# akabeacon_circle_ble113.net
KiCad netlist of a schematic drawn in EAGLE
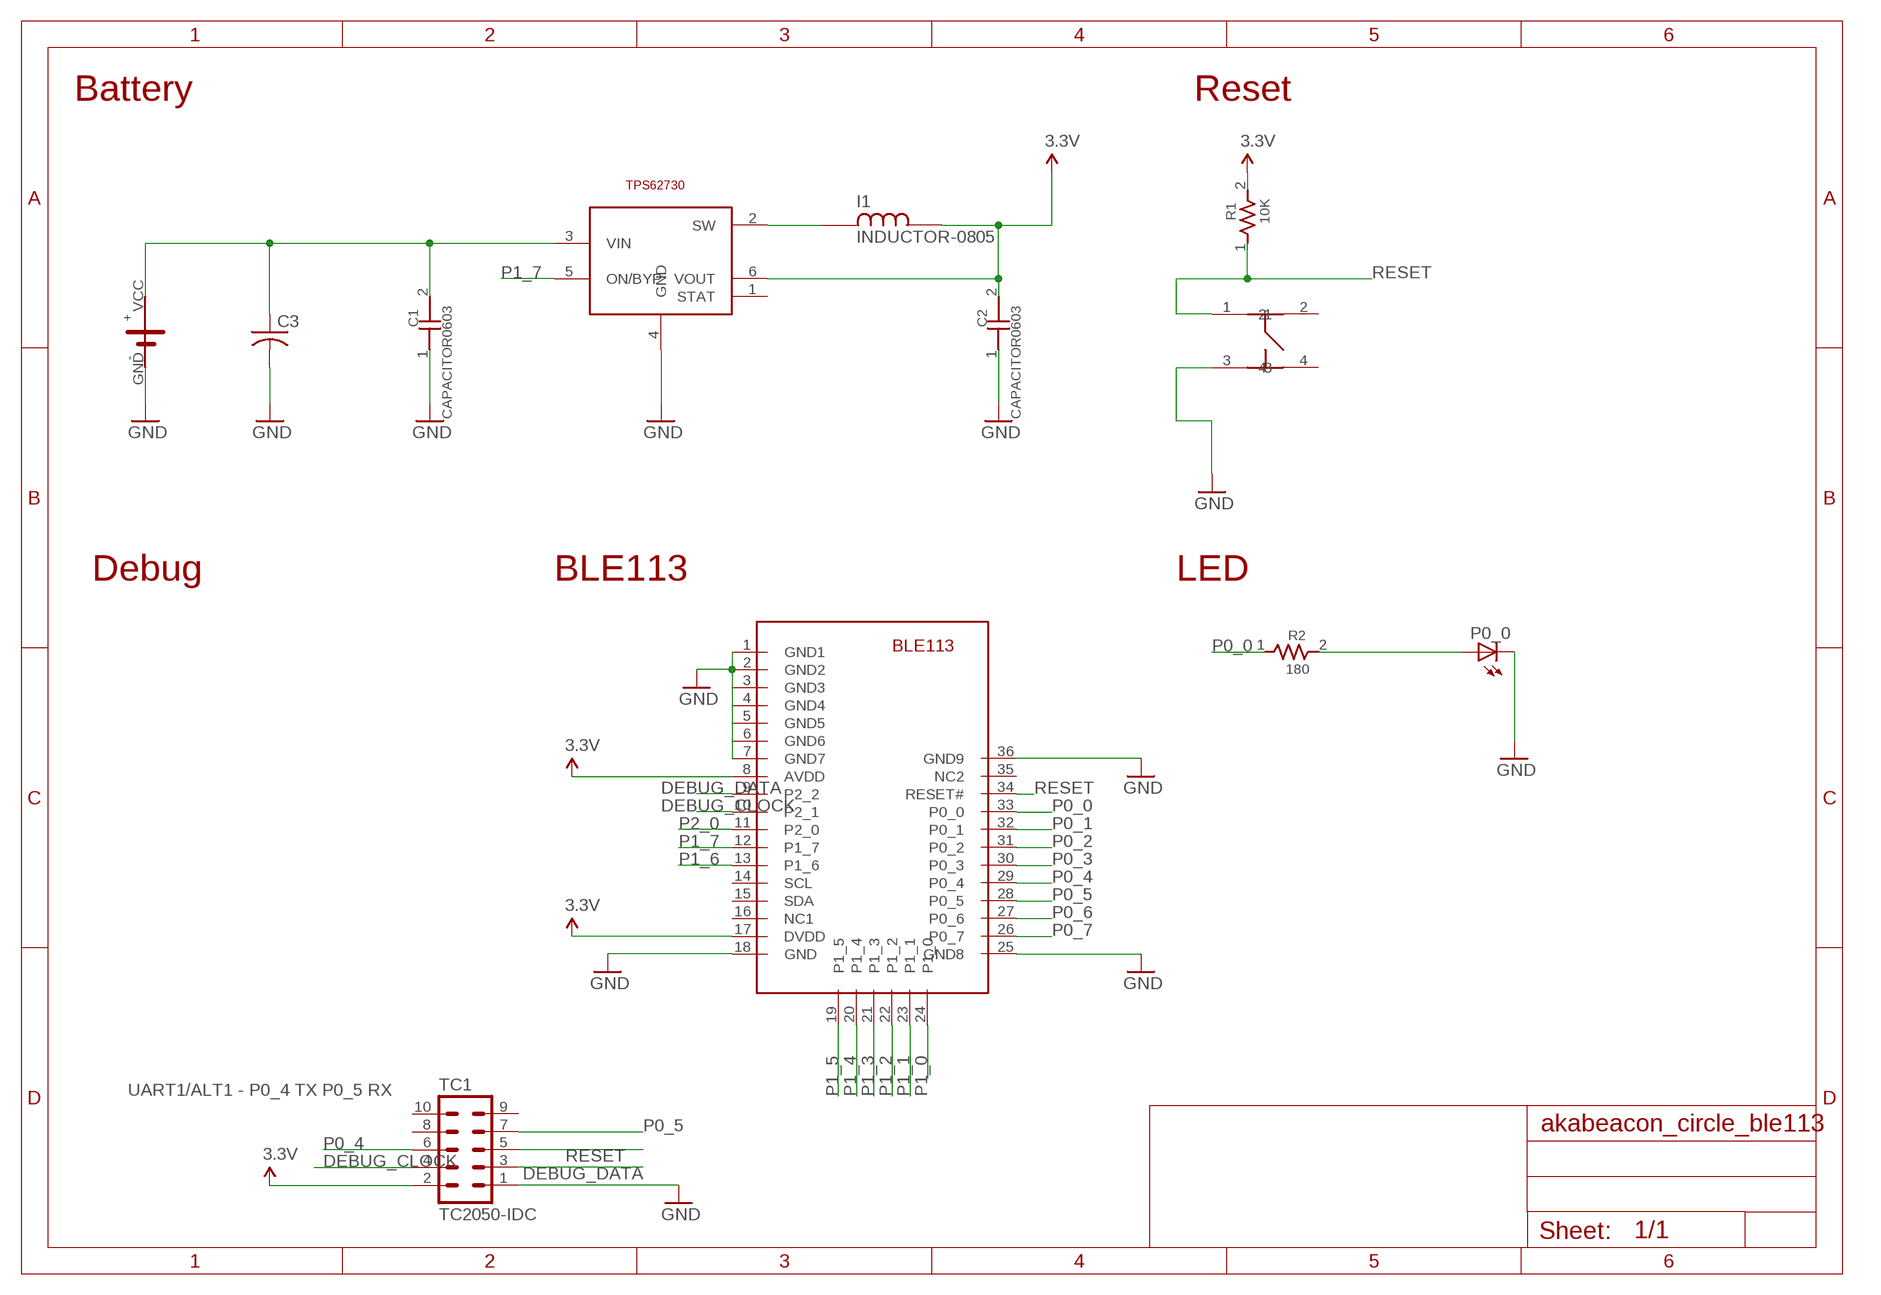
[diagram p0: schematic, sheet 1]

(export (version "E")
  (design (tool "Eeschema 10.0.6"))
  (components
    (comp (ref "C1")
      (value "CAPACITOR0603")
      (footprint "eagle-import:0603")
      (libsource (lib "eagle-import") (part "CAPACITOR0603"))
    )
    (comp (ref "C2")
      (value "CAPACITOR0603")
      (footprint "eagle-import:0603")
      (libsource (lib "eagle-import") (part "CAPACITOR0603"))
    )
    (comp (ref "C3")
      (value "C-USC3225")
      (footprint "eagle-import:C3225")
      (libsource (lib "eagle-import") (part "C-USC3225"))
    )
    (comp (ref "I1")
      (value "INDUCTOR-0805")
      (footprint "eagle-import:INDUCTOR-0805")
      (libsource (lib "eagle-import") (part "INDUCTOR-0805"))
    )
    (comp (ref "P0_0")
      (value "LEDCHIP-LED0603")
      (footprint "eagle-import:CHIP-LED0603")
      (libsource (lib "eagle-import") (part "LEDCHIP-LED0603"))
    )
    (comp (ref "R1")
      (value "10K")
      (footprint "eagle-import:0603")
      (libsource (lib "eagle-import") (part "RESISTOR0603"))
    )
    (comp (ref "R2")
      (value "180")
      (footprint "eagle-import:0603")
      (libsource (lib "eagle-import") (part "RESISTOR0603"))
    )
    (comp (ref "TC1")
      (value "TC2050-IDC")
      (footprint "eagle-import:TC2050-IDC-NL")
      (libsource (lib "eagle-import") (part "TC2050-IDC"))
    )
    (comp (ref "TPS1")
      (value "TI-TPS62730")
      (footprint "eagle-import:TI-TPS62730")
      (libsource (lib "eagle-import") (part "TI-TPS62730"))
    )
    (comp (ref "U$1")
      (value "CIRCLE-TYPE1")
      (footprint "eagle-import:CIRCLE-TYE1-TC2030")
      (libsource (lib "eagle-import") (part "CIRCLE-TYPE1"))
    )
    (comp (ref "U$4")
      (value "BLE113")
      (footprint "eagle-import:BLE113")
      (libsource (lib "eagle-import") (part "BLE113"))
    )
    (comp (ref "U$5")
      (value "SWICTH-4P(KMR2)")
      (footprint "eagle-import:SWITCH-4P(KMR2)")
      (libsource (lib "eagle-import") (part "SWICTH-4P(KMR2)"))
    )
  )
  (nets
    (net (code "1") (name "/DEBUG_CLOCK") (class "Default")
      (node (ref "TC1") (pin "4") (pinfunction "4_4") (pintype "passive"))
      (node (ref "U$4") (pin "10") (pinfunction "P2_1_10") (pintype "bidirectional"))
    )
    (net (code "2") (name "/DEBUG_DATA") (class "Default")
      (node (ref "TC1") (pin "3") (pinfunction "3_3") (pintype "passive"))
      (node (ref "U$4") (pin "9") (pinfunction "P2_2_9") (pintype "bidirectional"))
    )
    (net (code "3") (name "/P0_0") (class "Default")
      (node (ref "R2") (pin "1") (pinfunction "1_1") (pintype "passive"))
      (node (ref "U$4") (pin "33") (pinfunction "P0_0_33") (pintype "bidirectional"))
    )
    (net (code "4") (name "/P0_1") (class "Default")
      (node (ref "U$4") (pin "32") (pinfunction "P0_1_32") (pintype "bidirectional"))
    )
    (net (code "5") (name "/P0_2") (class "Default")
      (node (ref "U$4") (pin "31") (pinfunction "P0_2_31") (pintype "bidirectional"))
    )
    (net (code "6") (name "/P0_3") (class "Default")
      (node (ref "U$4") (pin "30") (pinfunction "P0_3_30") (pintype "bidirectional"))
    )
    (net (code "7") (name "/P0_4") (class "Default")
      (node (ref "TC1") (pin "6") (pinfunction "6_6") (pintype "passive"))
      (node (ref "U$4") (pin "29") (pinfunction "P0_4_29") (pintype "bidirectional"))
    )
    (net (code "8") (name "/P0_5") (class "Default")
      (node (ref "TC1") (pin "7") (pinfunction "7_7") (pintype "passive"))
      (node (ref "U$4") (pin "28") (pinfunction "P0_5_28") (pintype "bidirectional"))
    )
    (net (code "9") (name "/P0_6") (class "Default")
      (node (ref "U$4") (pin "27") (pinfunction "P0_6_27") (pintype "bidirectional"))
    )
    (net (code "10") (name "/P0_7") (class "Default")
      (node (ref "U$4") (pin "26") (pinfunction "P0_7_26") (pintype "bidirectional"))
    )
    (net (code "11") (name "/P1_0") (class "Default")
      (node (ref "U$4") (pin "24") (pinfunction "P1_0_24") (pintype "bidirectional"))
    )
    (net (code "12") (name "/P1_1") (class "Default")
      (node (ref "U$4") (pin "23") (pinfunction "P1_1_23") (pintype "bidirectional"))
    )
    (net (code "13") (name "/P1_2") (class "Default")
      (node (ref "U$4") (pin "22") (pinfunction "P1_2_22") (pintype "bidirectional"))
    )
    (net (code "14") (name "/P1_3") (class "Default")
      (node (ref "U$4") (pin "21") (pinfunction "P1_3_21") (pintype "bidirectional"))
    )
    (net (code "15") (name "/P1_4") (class "Default")
      (node (ref "U$4") (pin "20") (pinfunction "P1_4_20") (pintype "bidirectional"))
    )
    (net (code "16") (name "/P1_5") (class "Default")
      (node (ref "U$4") (pin "19") (pinfunction "P1_5_19") (pintype "bidirectional"))
    )
    (net (code "17") (name "/P1_6") (class "Default")
      (node (ref "U$4") (pin "13") (pinfunction "P1_6_13") (pintype "bidirectional"))
    )
    (net (code "18") (name "/P1_7") (class "Default")
      (node (ref "TPS1") (pin "5") (pinfunction "ON/BYP_5") (pintype "bidirectional"))
      (node (ref "U$4") (pin "12") (pinfunction "P1_7_12") (pintype "bidirectional"))
    )
    (net (code "19") (name "/P2_0") (class "Default")
      (node (ref "U$4") (pin "11") (pinfunction "P2_0_11") (pintype "bidirectional"))
    )
    (net (code "20") (name "/RESET") (class "Default")
      (node (ref "R1") (pin "1") (pinfunction "1_1") (pintype "passive"))
      (node (ref "TC1") (pin "5") (pinfunction "5_5") (pintype "passive"))
      (node (ref "U$4") (pin "34") (pinfunction "RESET#_34") (pintype "bidirectional"))
      (node (ref "U$5") (pin "1") (pinfunction "1_1") (pintype "bidirectional"))
    )
    (net (code "21") (name "3.3V") (class "Default")
      (node (ref "C2") (pin "2") (pinfunction "2_2") (pintype "passive"))
      (node (ref "I1") (pin "P$2") (pinfunction "P$2_P$2") (pintype "bidirectional"))
      (node (ref "R1") (pin "2") (pinfunction "2_2") (pintype "passive"))
      (node (ref "TC1") (pin "2") (pinfunction "2_2") (pintype "passive"))
      (node (ref "TPS1") (pin "6") (pinfunction "VOUT_6") (pintype "bidirectional"))
      (node (ref "U$4") (pin "17") (pinfunction "DVDD_17") (pintype "bidirectional"))
      (node (ref "U$4") (pin "8") (pinfunction "AVDD_8") (pintype "bidirectional"))
    )
    (net (code "22") (name "GND") (class "Default")
      (node (ref "C1") (pin "1") (pinfunction "1_1") (pintype "passive"))
      (node (ref "C2") (pin "1") (pinfunction "1_1") (pintype "passive"))
      (node (ref "C3") (pin "2") (pinfunction "2_2") (pintype "passive"))
      (node (ref "P0_0") (pin "C") (pinfunction "C_C") (pintype "passive"))
      (node (ref "TC1") (pin "1") (pinfunction "1_1") (pintype "passive"))
      (node (ref "TPS1") (pin "4") (pinfunction "GND_4") (pintype "bidirectional"))
      (node (ref "U$1") (pin "GND") (pinfunction "GND_GND") (pintype "bidirectional"))
      (node (ref "U$4") (pin "1") (pinfunction "GND1_1") (pintype "bidirectional"))
      (node (ref "U$4") (pin "18") (pinfunction "GND_18") (pintype "bidirectional"))
      (node (ref "U$4") (pin "2") (pinfunction "GND2_2") (pintype "bidirectional"))
      (node (ref "U$4") (pin "25") (pinfunction "GND8_25") (pintype "bidirectional"))
      (node (ref "U$4") (pin "3") (pinfunction "GND3_3") (pintype "bidirectional"))
      (node (ref "U$4") (pin "36") (pinfunction "GND9_36") (pintype "bidirectional"))
      (node (ref "U$4") (pin "4") (pinfunction "GND4_4") (pintype "bidirectional"))
      (node (ref "U$4") (pin "5") (pinfunction "GND5_5") (pintype "bidirectional"))
      (node (ref "U$4") (pin "6") (pinfunction "GND6_6") (pintype "bidirectional"))
      (node (ref "U$4") (pin "7") (pinfunction "GND7_7") (pintype "bidirectional"))
      (node (ref "U$5") (pin "3") (pinfunction "3_3") (pintype "bidirectional"))
    )
    (net (code "23") (name "Net-(P0_0-PadA)") (class "Default")
      (node (ref "P0_0") (pin "A") (pinfunction "A_A") (pintype "passive"))
      (node (ref "R2") (pin "2") (pinfunction "2_2") (pintype "passive"))
    )
    (net (code "24") (name "Net-(TPS1-SW)") (class "Default")
      (node (ref "I1") (pin "P$1") (pinfunction "P$1_P$1") (pintype "bidirectional"))
      (node (ref "TPS1") (pin "2") (pinfunction "SW_2") (pintype "bidirectional"))
    )
    (net (code "25") (name "Net-(TPS1-VIN)") (class "Default")
      (node (ref "C1") (pin "2") (pinfunction "2_2") (pintype "passive"))
      (node (ref "C3") (pin "1") (pinfunction "1_1") (pintype "passive"))
      (node (ref "TPS1") (pin "3") (pinfunction "VIN_3") (pintype "bidirectional"))
      (node (ref "U$1") (pin "VCC") (pinfunction "VCC_VCC") (pintype "bidirectional"))
    )
    (net (code "26") (name "unconnected-(TC1-Pad8)") (class "Default")
      (node (ref "TC1") (pin "8") (pinfunction "8_8") (pintype "passive"))
    )
    (net (code "27") (name "unconnected-(TC1-Pad9)") (class "Default")
      (node (ref "TC1") (pin "9") (pinfunction "9_9") (pintype "passive"))
    )
    (net (code "28") (name "unconnected-(TC1-Pad10)") (class "Default")
      (node (ref "TC1") (pin "10") (pinfunction "10_10") (pintype "passive"))
    )
    (net (code "29") (name "unconnected-(TPS1-STAT-Pad1)") (class "Default")
      (node (ref "TPS1") (pin "1") (pinfunction "STAT_1") (pintype "bidirectional"))
    )
    (net (code "30") (name "unconnected-(U$4-NC1-Pad16)") (class "Default")
      (node (ref "U$4") (pin "16") (pinfunction "NC1_16") (pintype "bidirectional"))
    )
    (net (code "31") (name "unconnected-(U$4-NC2-Pad35)") (class "Default")
      (node (ref "U$4") (pin "35") (pinfunction "NC2_35") (pintype "bidirectional"))
    )
    (net (code "32") (name "unconnected-(U$4-SCL-Pad14)") (class "Default")
      (node (ref "U$4") (pin "14") (pinfunction "SCL_14") (pintype "bidirectional"))
    )
    (net (code "33") (name "unconnected-(U$4-SDA-Pad15)") (class "Default")
      (node (ref "U$4") (pin "15") (pinfunction "SDA_15") (pintype "bidirectional"))
    )
    (net (code "34") (name "unconnected-(U$5-Pad2)") (class "Default")
      (node (ref "U$5") (pin "2") (pinfunction "2_2") (pintype "bidirectional"))
    )
    (net (code "35") (name "unconnected-(U$5-Pad4)") (class "Default")
      (node (ref "U$5") (pin "4") (pinfunction "4_4") (pintype "bidirectional"))
    )
  )
)
